# DRS_SCH-05-16.net
KiCad netlist of a schematic drawn in Altium Designer
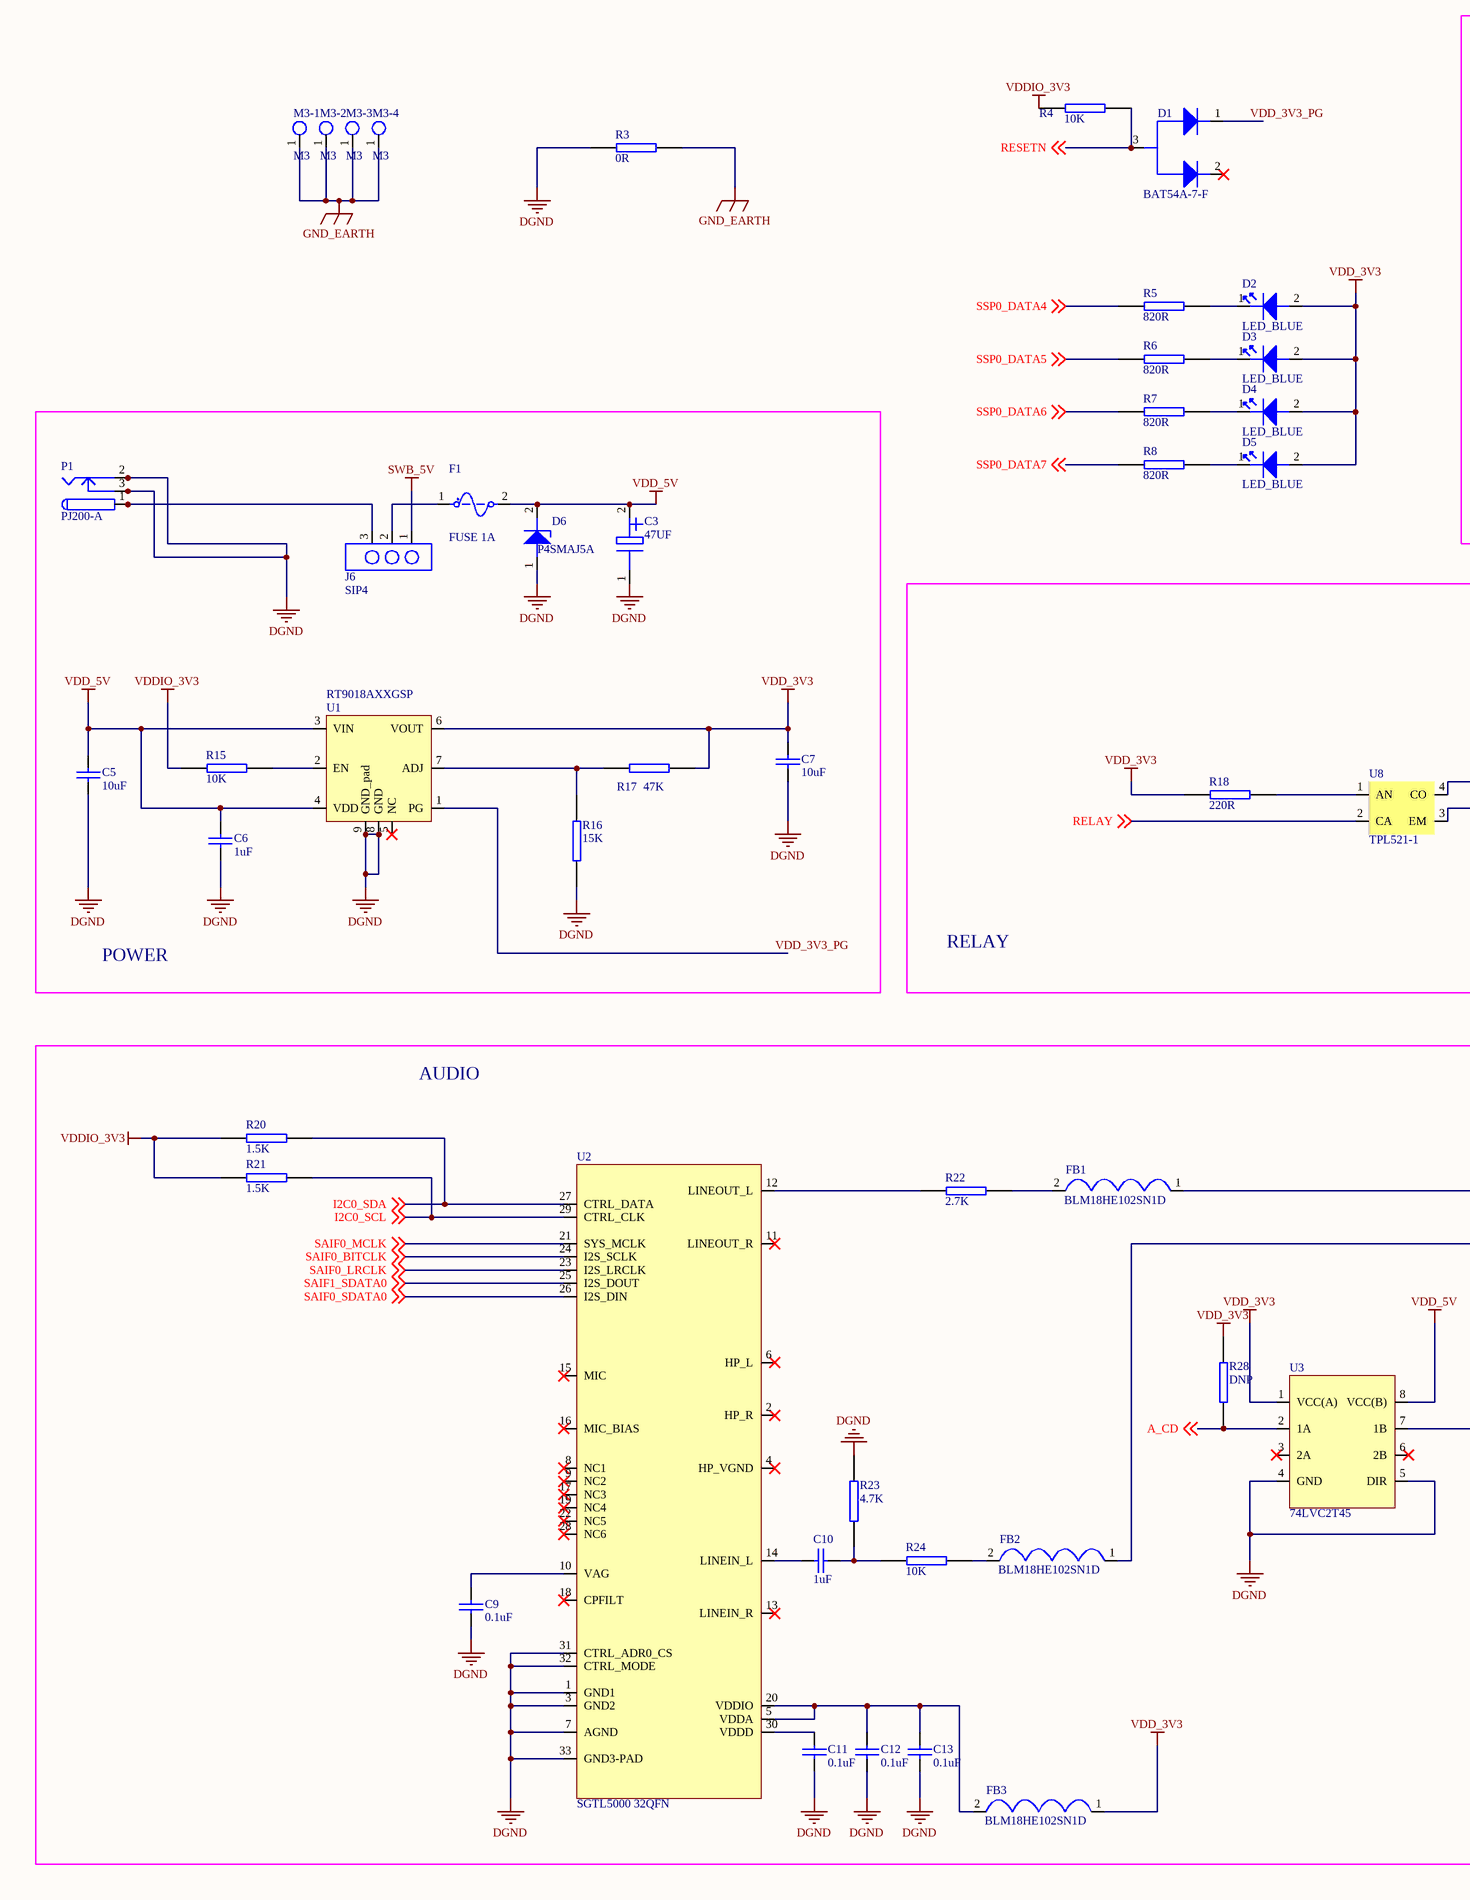
[diagram p0: DRS_SCH-05-16.SchDoc, left]
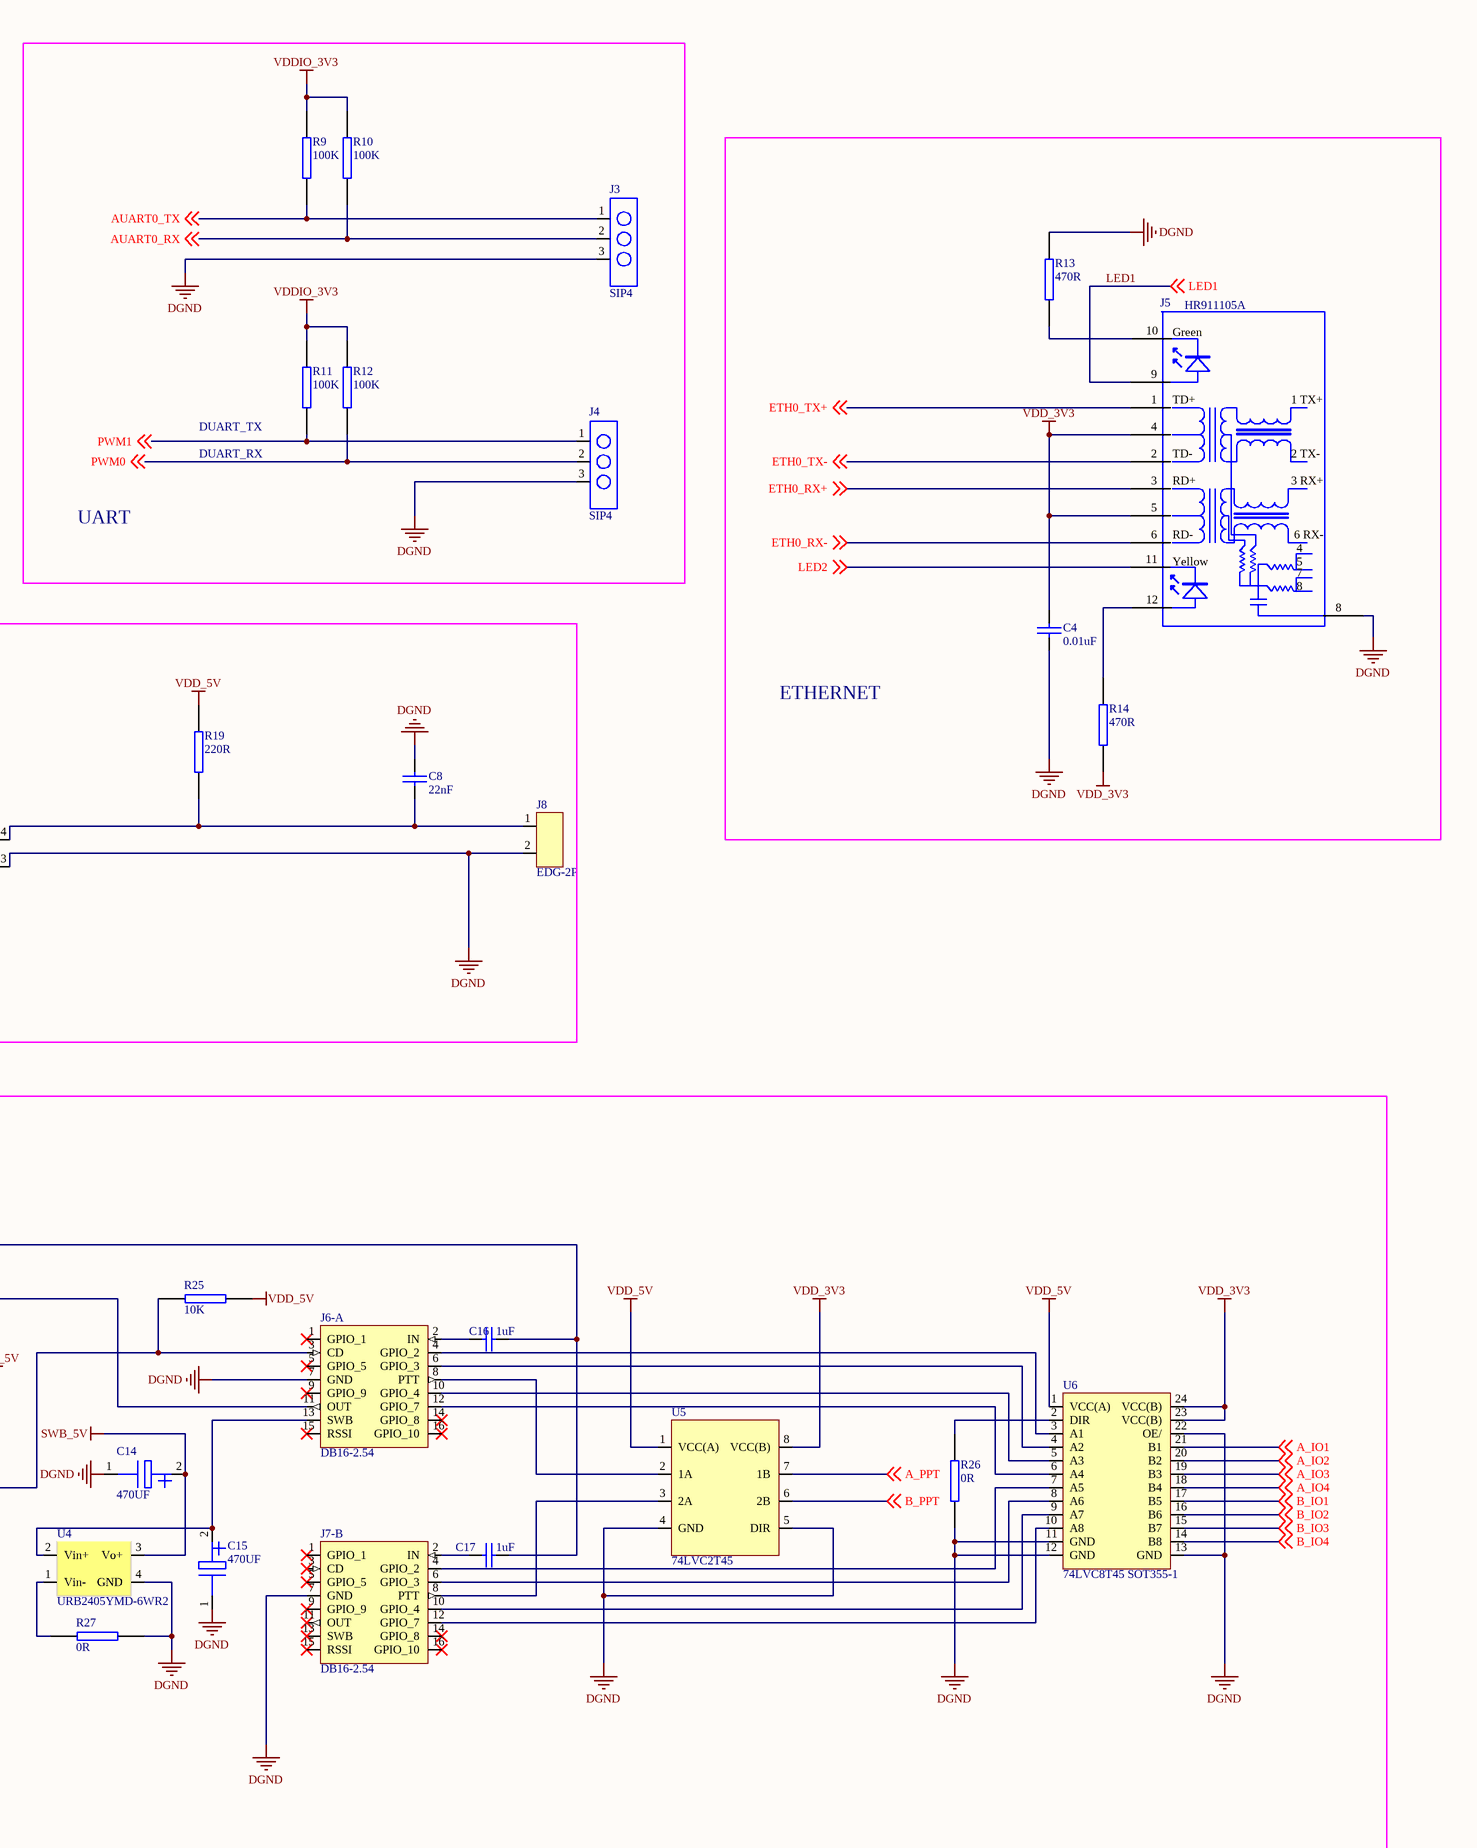
[diagram p1: DRS_SCH-05-16.SchDoc, right]

(export (version "E")
  (design (tool "Eeschema 10.0.6"))
  (components
    (comp (ref "C3") (value "47UF") (footprint "RVT6.3") (libsource (lib "Schlib1") (part "7343")))
    (comp (ref "C4")
      (value "0.01uF")
      (footprint "0603")
      (description "Capacitor")
      (libsource (lib "AirGateway") (part "CAP"))
    )
    (comp (ref "C5")
      (value "10uF")
      (footprint "C0805")
      (description "Capacitor")
      (libsource (lib "AirGateway") (part "CAP"))
    )
    (comp (ref "C6")
      (value "1uF")
      (footprint "0603")
      (description "Capacitor")
      (libsource (lib "AirGateway") (part "CAP"))
    )
    (comp (ref "C7")
      (value "10uF")
      (footprint "C0805")
      (description "Capacitor")
      (libsource (lib "AirGateway") (part "CAP"))
    )
    (comp (ref "C8")
      (value "22nF")
      (footprint "0603")
      (description "Capacitor")
      (libsource (lib "AirGateway") (part "CAP"))
    )
    (comp (ref "C9")
      (value "0.1uF")
      (footprint "0603")
      (description "Capacitor")
      (libsource (lib "AirGateway") (part "CAP"))
    )
    (comp (ref "C10")
      (value "1uF")
      (footprint "0603")
      (description "Capacitor")
      (libsource (lib "AirGateway") (part "CAP"))
    )
    (comp (ref "C11")
      (value "0.1uF")
      (footprint "0603")
      (description "Capacitor")
      (libsource (lib "AirGateway") (part "CAP"))
    )
    (comp (ref "C12")
      (value "0.1uF")
      (footprint "0603")
      (description "Capacitor")
      (libsource (lib "AirGateway") (part "CAP"))
    )
    (comp (ref "C13")
      (value "0.1uF")
      (footprint "0603")
      (description "Capacitor")
      (libsource (lib "AirGateway") (part "CAP"))
    )
    (comp (ref "C14") (value "470UF") (footprint "RVT8") (libsource (lib "Schlib1") (part "7343")))
    (comp (ref "C15") (value "470UF") (footprint "RVT8") (libsource (lib "Schlib1") (part "7343")))
    (comp (ref "C16")
      (value "1uF")
      (footprint "0603")
      (description "Capacitor")
      (libsource (lib "AirGateway") (part "CAP"))
    )
    (comp (ref "C17")
      (value "1uF")
      (footprint "0603")
      (description "Capacitor")
      (libsource (lib "AirGateway") (part "CAP"))
    )
    (comp (ref "D1") (value "BAT54A-7-F") (footprint "S9013") (libsource (lib "Schlib1") (part "BAT54A-7-F")))
    (comp (ref "D2") (value "LED_BLUE") (footprint "LED_BLUE") (libsource (lib "Schlib1") (part "LED_BLUE")))
    (comp (ref "D3") (value "LED_BLUE") (footprint "LED_BLUE") (libsource (lib "Schlib1") (part "LED_BLUE")))
    (comp (ref "D4") (value "LED_BLUE") (footprint "LED_BLUE") (libsource (lib "Schlib1") (part "LED_BLUE")))
    (comp (ref "D5") (value "LED_BLUE") (footprint "LED_BLUE") (libsource (lib "Schlib1") (part "LED_BLUE")))
    (comp (ref "D6") (value "P4SMAJ5A") (footprint "P4SMAJ5A") (libsource (lib "Schlib1") (part "P4SMAJ5A")))
    (comp (ref "F1") (value "FUSE 1A") (footprint "FUSE 1A") (libsource (lib "Schlib1") (part "FUSE 1A")))
    (comp (ref "FB1")
      (value "BLM18HE102SN1D")
      (footprint "0603")
      (libsource (lib "Schlib1") (part "BLM18HE102SN1D"))
    )
    (comp (ref "FB2")
      (value "BLM18HE102SN1D")
      (footprint "0603")
      (libsource (lib "Schlib1") (part "BLM18HE102SN1D"))
    )
    (comp (ref "FB3")
      (value "BLM18HE102SN1D")
      (footprint "0603")
      (libsource (lib "Schlib1") (part "BLM18HE102SN1D"))
    )
    (comp (ref "J3") (value "SIP4") (footprint "SIP3") (libsource (lib "Schlib1") (part "SIP4")))
    (comp (ref "J4") (value "SIP4") (footprint "SIP3") (libsource (lib "Schlib1") (part "SIP4")))
    (comp (ref "J5")
      (value "HR911105A")
      (footprint "HR911105A")
      (libsource (lib "AirGateway") (part "HR911105A"))
    )
    (comp (ref "J6") (value "SIP4") (footprint "SIP3") (libsource (lib "Schlib1") (part "SIP4")))
    (comp (ref "J6-A")
      (value "DB16-2.54")
      (footprint "DB2X8-2.54")
      (libsource (lib "Schlib1") (part "DB16-2.54"))
    )
    (comp (ref "J7-B")
      (value "DB16-2.54")
      (footprint "DB2X8-2.54")
      (libsource (lib "Schlib1") (part "DB16-2.54"))
    )
    (comp (ref "J8")
      (value "EDG-2P")
      (footprint "LZ1R-5.08-02P-140")
      (libsource (lib "Schlib1") (part "EDG-2P"))
    )
    (comp (ref "M3-1") (value "M3") (footprint "M3") (libsource (lib "Schlib1") (part "M3")))
    (comp (ref "M3-2") (value "M3") (footprint "M3") (libsource (lib "Schlib1") (part "M3")))
    (comp (ref "M3-3") (value "M3") (footprint "M3") (libsource (lib "Schlib1") (part "M3")))
    (comp (ref "M3-4") (value "M3") (footprint "M3") (libsource (lib "Schlib1") (part "M3")))
    (comp (ref "P1")
      (value "PJ200-A")
      (footprint "KLD-0202")
      (description "Low Voltage Power Supply Connector")
      (fields (field (name "PUBLISHER") "Altium Limited"))
      (libsource (lib "Miscellaneous Connectors") (part "PWR2.5"))
    )
    (comp (ref "R3") (value "0R") (footprint "0603") (libsource (lib "AirGateway") (part "RES2")))
    (comp (ref "R4") (value "10K") (footprint "0603") (libsource (lib "AirGateway") (part "RES2")))
    (comp (ref "R5") (value "820R") (footprint "0603") (libsource (lib "AirGateway") (part "RES2")))
    (comp (ref "R6") (value "820R") (footprint "0603") (libsource (lib "AirGateway") (part "RES2")))
    (comp (ref "R7") (value "820R") (footprint "0603") (libsource (lib "AirGateway") (part "RES2")))
    (comp (ref "R8") (value "820R") (footprint "0603") (libsource (lib "AirGateway") (part "RES2")))
    (comp (ref "R9") (value "100K") (footprint "0603") (libsource (lib "AirGateway") (part "RES2")))
    (comp (ref "R10") (value "100K") (footprint "0603") (libsource (lib "AirGateway") (part "RES2")))
    (comp (ref "R11") (value "100K") (footprint "0603") (libsource (lib "AirGateway") (part "RES2")))
    (comp (ref "R12") (value "100K") (footprint "0603") (libsource (lib "AirGateway") (part "RES2")))
    (comp (ref "R13") (value "470R") (footprint "0603") (libsource (lib "AirGateway") (part "RES2")))
    (comp (ref "R14") (value "470R") (footprint "0603") (libsource (lib "AirGateway") (part "RES2")))
    (comp (ref "R15") (value "10K") (footprint "0603") (libsource (lib "AirGateway") (part "RES2")))
    (comp (ref "R16") (value "15K") (footprint "0603") (libsource (lib "AirGateway") (part "RES2")))
    (comp (ref "R17") (value "47K") (footprint "0603") (libsource (lib "AirGateway") (part "RES2")))
    (comp (ref "R18") (value "220R") (footprint "0603") (libsource (lib "AirGateway") (part "RES2")))
    (comp (ref "R19") (value "220R") (footprint "0603") (libsource (lib "AirGateway") (part "RES2")))
    (comp (ref "R20") (value "1.5K") (footprint "0603") (libsource (lib "AirGateway") (part "RES2")))
    (comp (ref "R21") (value "1.5K") (footprint "0603") (libsource (lib "AirGateway") (part "RES2")))
    (comp (ref "R22") (value "2.7K") (footprint "0603") (libsource (lib "AirGateway") (part "RES2")))
    (comp (ref "R23") (value "4.7K") (footprint "0603") (libsource (lib "AirGateway") (part "RES2")))
    (comp (ref "R24") (value "10K") (footprint "0603") (libsource (lib "AirGateway") (part "RES2")))
    (comp (ref "R25") (value "10K") (footprint "0603") (libsource (lib "AirGateway") (part "RES2")))
    (comp (ref "R26") (value "0R") (footprint "0603") (libsource (lib "AirGateway") (part "RES2")))
    (comp (ref "R27") (value "0R") (footprint "0603") (libsource (lib "AirGateway") (part "RES2")))
    (comp (ref "R28") (value "DNP") (footprint "0603") (libsource (lib "AirGateway") (part "RES2")))
    (comp (ref "U1")
      (value "RT9018AXXGSP")
      (footprint "RT9018")
      (libsource (lib "Schlib1") (part "RT9018AXXGSP"))
    )
    (comp (ref "U2")
      (value "SGTL5000 32QFN")
      (footprint "SGTL5000 32QFN")
      (libsource (lib "Schlib1") (part "SGTL5000 32QFN"))
    )
    (comp (ref "U3")
      (value "74LVC2T45")
      (footprint "74LVC2T45")
      (libsource (lib "Schlib1") (part "74LVC2T45"))
    )
    (comp (ref "U4")
      (value "URB2405YMD-6WR2")
      (footprint "URB2405YMD-6WR2")
      (libsource (lib "Schlib1") (part "URB2405YMD-6WR2"))
    )
    (comp (ref "U5")
      (value "74LVC2T45")
      (footprint "74LVC2T45")
      (libsource (lib "Schlib1") (part "74LVC2T45"))
    )
    (comp (ref "U6")
      (value "74LVC8T45 SOT355-1")
      (footprint "74LVC8T245")
      (libsource (lib "Schlib1") (part "74LVC8T45 SOT355-1"))
    )
    (comp (ref "U8") (value "TPL521-1") (footprint "TPL521-1") (libsource (lib "Schlib1") (part "TPL521-1")))
  )
  (nets
    (net (code "1") (name "/VDD_3V3_PG") (class "Default")
      (node (ref "D1") (pin "1") (pintype "passive"))
      (node (ref "U1") (pin "1") (pinfunction "PG_1") (pintype "passive"))
    )
    (net (code "2") (name "AUART0_RX") (class "Default")
      (node (ref "J3") (pin "2") (pintype "passive"))
      (node (ref "R10") (pin "1") (pinfunction "1_1") (pintype "passive"))
    )
    (net (code "3") (name "AUART0_TX") (class "Default")
      (node (ref "J3") (pin "1") (pintype "passive"))
      (node (ref "R9") (pin "1") (pinfunction "1_1") (pintype "passive"))
    )
    (net (code "4") (name "A_CD") (class "Default")
      (node (ref "R28") (pin "2") (pinfunction "2_2") (pintype "passive"))
      (node (ref "U3") (pin "2") (pinfunction "1A_2") (pintype "passive"))
    )
    (net (code "5") (name "A_IO1") (class "Default")
      (node (ref "U6") (pin "21") (pinfunction "B1_21") (pintype "passive"))
    )
    (net (code "6") (name "A_IO2") (class "Default")
      (node (ref "U6") (pin "20") (pinfunction "B2_20") (pintype "passive"))
    )
    (net (code "7") (name "A_IO3") (class "Default")
      (node (ref "U6") (pin "19") (pinfunction "B3_19") (pintype "passive"))
    )
    (net (code "8") (name "A_IO4") (class "Default")
      (node (ref "U6") (pin "18") (pinfunction "B4_18") (pintype "passive"))
    )
    (net (code "9") (name "A_PPT") (class "Default")
      (node (ref "U5") (pin "7") (pinfunction "1B_7") (pintype "passive"))
    )
    (net (code "10") (name "B_IO1") (class "Default")
      (node (ref "U6") (pin "17") (pinfunction "B5_17") (pintype "passive"))
    )
    (net (code "11") (name "B_IO2") (class "Default")
      (node (ref "U6") (pin "16") (pinfunction "B6_16") (pintype "passive"))
    )
    (net (code "12") (name "B_IO3") (class "Default")
      (node (ref "U6") (pin "15") (pinfunction "B7_15") (pintype "passive"))
    )
    (net (code "13") (name "B_IO4") (class "Default")
      (node (ref "U6") (pin "14") (pinfunction "B8_14") (pintype "passive"))
    )
    (net (code "14") (name "B_PPT") (class "Default")
      (node (ref "U5") (pin "6") (pinfunction "2B_6") (pintype "passive"))
    )
    (net (code "15") (name "DGND") (class "Default")
      (node (ref "C11") (pin "2") (pinfunction "2_2") (pintype "passive"))
      (node (ref "C12") (pin "2") (pinfunction "2_2") (pintype "passive"))
      (node (ref "C13") (pin "2") (pinfunction "2_2") (pintype "passive"))
      (node (ref "C14") (pin "1") (pintype "passive"))
      (node (ref "C15") (pin "1") (pintype "passive"))
      (node (ref "C3") (pin "1") (pintype "passive"))
      (node (ref "C4") (pin "2") (pinfunction "2_2") (pintype "passive"))
      (node (ref "C5") (pin "2") (pinfunction "2_2") (pintype "passive"))
      (node (ref "C6") (pin "2") (pinfunction "2_2") (pintype "passive"))
      (node (ref "C7") (pin "2") (pinfunction "2_2") (pintype "passive"))
      (node (ref "C8") (pin "1") (pinfunction "1_1") (pintype "passive"))
      (node (ref "C9") (pin "1") (pinfunction "1_1") (pintype "passive"))
      (node (ref "D6") (pin "1") (pintype "passive"))
      (node (ref "J3") (pin "3") (pintype "passive"))
      (node (ref "J4") (pin "3") (pintype "passive"))
      (node (ref "J5") (pin "8") (pintype "passive"))
      (node (ref "J6-A") (pin "7") (pinfunction "GND_7") (pintype "passive"))
      (node (ref "J7-B") (pin "7") (pinfunction "GND_7") (pintype "passive"))
      (node (ref "J8") (pin "2") (pintype "passive"))
      (node (ref "P1") (pin "2") (pinfunction "2_2") (pintype "power_in"))
      (node (ref "P1") (pin "2A") (pinfunction "2A_2A") (pintype "power_in"))
      (node (ref "P1") (pin "2B") (pinfunction "2B_2B") (pintype "power_in"))
      (node (ref "P1") (pin "3") (pinfunction "3_3") (pintype "power_in"))
      (node (ref "P1") (pin "3A") (pinfunction "3A_3A") (pintype "power_in"))
      (node (ref "P1") (pin "3B") (pinfunction "3B_3B") (pintype "power_in"))
      (node (ref "R13") (pin "2") (pinfunction "2_2") (pintype "passive"))
      (node (ref "R16") (pin "1") (pinfunction "1_1") (pintype "passive"))
      (node (ref "R23") (pin "2") (pinfunction "2_2") (pintype "passive"))
      (node (ref "R26") (pin "1") (pinfunction "1_1") (pintype "passive"))
      (node (ref "R27") (pin "1") (pinfunction "1_1") (pintype "passive"))
      (node (ref "R3") (pin "2") (pinfunction "2_2") (pintype "passive"))
      (node (ref "U1") (pin "8") (pinfunction "GND_8") (pintype "passive"))
      (node (ref "U1") (pin "9") (pinfunction "GND_pad_9") (pintype "passive"))
      (node (ref "U2") (pin "1") (pinfunction "GND1_1") (pintype "passive"))
      (node (ref "U2") (pin "3") (pinfunction "GND2_3") (pintype "passive"))
      (node (ref "U2") (pin "31") (pinfunction "CTRL_ADR0_CS_31") (pintype "passive"))
      (node (ref "U2") (pin "32") (pinfunction "CTRL_MODE_32") (pintype "passive"))
      (node (ref "U2") (pin "33") (pinfunction "GND3-PAD_33") (pintype "passive"))
      (node (ref "U2") (pin "7") (pinfunction "AGND_7") (pintype "passive"))
      (node (ref "U3") (pin "4") (pinfunction "GND_4") (pintype "passive"))
      (node (ref "U3") (pin "5") (pinfunction "DIR_5") (pintype "passive"))
      (node (ref "U4") (pin "4") (pinfunction "GND_4") (pintype "passive"))
      (node (ref "U5") (pin "4") (pinfunction "GND_4") (pintype "passive"))
      (node (ref "U5") (pin "5") (pinfunction "DIR_5") (pintype "passive"))
      (node (ref "U6") (pin "11") (pinfunction "GND_11") (pintype "passive"))
      (node (ref "U6") (pin "12") (pinfunction "GND_12") (pintype "passive"))
      (node (ref "U6") (pin "13") (pinfunction "GND_13") (pintype "passive"))
      (node (ref "U6") (pin "22") (pinfunction "OE/_22") (pintype "passive"))
      (node (ref "U8") (pin "3") (pinfunction "EM_3") (pintype "passive"))
    )
    (net (code "16") (name "ETH0_RX+") (class "Default") (node (ref "J5") (pin "3") (pintype "passive")))
    (net (code "17") (name "ETH0_RX-") (class "Default") (node (ref "J5") (pin "6") (pintype "passive")))
    (net (code "18") (name "ETH0_TX+") (class "Default") (node (ref "J5") (pin "1") (pintype "passive")))
    (net (code "19") (name "ETH0_TX-") (class "Default") (node (ref "J5") (pin "2") (pintype "passive")))
    (net (code "20") (name "GND_EARTH") (class "Default")
      (node (ref "M3-1") (pin "1") (pintype "passive"))
      (node (ref "M3-2") (pin "1") (pintype "passive"))
      (node (ref "M3-3") (pin "1") (pintype "passive"))
      (node (ref "M3-4") (pin "1") (pintype "passive"))
      (node (ref "R3") (pin "1") (pinfunction "1_1") (pintype "passive"))
    )
    (net (code "21") (name "I2C0_SCL") (class "Default")
      (node (ref "R21") (pin "1") (pinfunction "1_1") (pintype "passive"))
      (node (ref "U2") (pin "29") (pinfunction "CTRL_CLK_29") (pintype "passive"))
    )
    (net (code "22") (name "I2C0_SDA") (class "Default")
      (node (ref "R20") (pin "1") (pinfunction "1_1") (pintype "passive"))
      (node (ref "U2") (pin "27") (pinfunction "CTRL_DATA_27") (pintype "passive"))
    )
    (net (code "23") (name "LED1") (class "Default") (node (ref "J5") (pin "9") (pintype "passive")))
    (net (code "24") (name "LED2") (class "Default") (node (ref "J5") (pin "11") (pintype "passive")))
    (net (code "25") (name "Net-(C10-Pad1)") (class "Default")
      (node (ref "C10") (pin "1") (pinfunction "1_1") (pintype "passive"))
      (node (ref "R23") (pin "1") (pinfunction "1_1") (pintype "passive"))
      (node (ref "R24") (pin "2") (pinfunction "2_2") (pintype "passive"))
    )
    (net (code "26") (name "Net-(C16-Pad1)") (class "Default")
      (node (ref "C16") (pin "1") (pinfunction "1_1") (pintype "passive"))
      (node (ref "C17") (pin "1") (pinfunction "1_1") (pintype "passive"))
      (node (ref "FB1") (pin "1") (pintype "passive"))
    )
    (net (code "27") (name "Net-(D2-Pad1)") (class "Default")
      (node (ref "D2") (pin "1") (pintype "passive"))
      (node (ref "R5") (pin "2") (pinfunction "2_2") (pintype "passive"))
    )
    (net (code "28") (name "Net-(D3-Pad1)") (class "Default")
      (node (ref "D3") (pin "1") (pintype "passive"))
      (node (ref "R6") (pin "2") (pinfunction "2_2") (pintype "passive"))
    )
    (net (code "29") (name "Net-(D4-Pad1)") (class "Default")
      (node (ref "D4") (pin "1") (pintype "passive"))
      (node (ref "R7") (pin "2") (pinfunction "2_2") (pintype "passive"))
    )
    (net (code "30") (name "Net-(D5-Pad1)") (class "Default")
      (node (ref "D5") (pin "1") (pintype "passive"))
      (node (ref "R8") (pin "2") (pinfunction "2_2") (pintype "passive"))
    )
    (net (code "31") (name "Net-(F1-Pad1)") (class "Default")
      (node (ref "F1") (pin "1") (pintype "passive"))
      (node (ref "J6") (pin "2") (pintype "passive"))
    )
    (net (code "32") (name "Net-(FB1-Pad2)") (class "Default")
      (node (ref "FB1") (pin "2") (pintype "passive"))
      (node (ref "R22") (pin "1") (pinfunction "1_1") (pintype "passive"))
    )
    (net (code "33") (name "Net-(FB2-Pad2)") (class "Default")
      (node (ref "FB2") (pin "2") (pintype "passive"))
      (node (ref "R24") (pin "1") (pinfunction "1_1") (pintype "passive"))
    )
    (net (code "34") (name "Net-(J5-Pad10)") (class "Default")
      (node (ref "J5") (pin "10") (pintype "passive"))
      (node (ref "R13") (pin "1") (pinfunction "1_1") (pintype "passive"))
    )
    (net (code "35") (name "Net-(J5-Pad12)") (class "Default")
      (node (ref "J5") (pin "12") (pintype "passive"))
      (node (ref "R14") (pin "2") (pinfunction "2_2") (pintype "passive"))
    )
    (net (code "36") (name "Net-(J6-A-CD)") (class "Default")
      (node (ref "J6-A") (pin "3") (pinfunction "CD_3") (pintype "input"))
      (node (ref "R25") (pin "2") (pinfunction "2_2") (pintype "passive"))
      (node (ref "U3") (pin "7") (pinfunction "1B_7") (pintype "passive"))
    )
    (net (code "37") (name "Net-(J6-A-GPIO_2)") (class "Default")
      (node (ref "J6-A") (pin "4") (pinfunction "GPIO_2_4") (pintype "passive"))
      (node (ref "U6") (pin "3") (pinfunction "A1_3") (pintype "passive"))
    )
    (net (code "38") (name "Net-(J6-A-GPIO_3)") (class "Default")
      (node (ref "J6-A") (pin "6") (pinfunction "GPIO_3_6") (pintype "passive"))
      (node (ref "U6") (pin "4") (pinfunction "A2_4") (pintype "passive"))
    )
    (net (code "39") (name "Net-(J6-A-GPIO_4)") (class "Default")
      (node (ref "J6-A") (pin "10") (pinfunction "GPIO_4_10") (pintype "passive"))
      (node (ref "U6") (pin "5") (pinfunction "A3_5") (pintype "passive"))
    )
    (net (code "40") (name "Net-(J6-A-GPIO_7)") (class "Default")
      (node (ref "J6-A") (pin "12") (pinfunction "GPIO_7_12") (pintype "passive"))
      (node (ref "U6") (pin "6") (pinfunction "A4_6") (pintype "passive"))
    )
    (net (code "41") (name "Net-(J6-A-IN)") (class "Default")
      (node (ref "C16") (pin "2") (pinfunction "2_2") (pintype "passive"))
      (node (ref "J6-A") (pin "2") (pinfunction "IN_2") (pintype "input"))
    )
    (net (code "42") (name "Net-(J6-A-OUT)") (class "Default")
      (node (ref "FB2") (pin "1") (pintype "passive"))
      (node (ref "J6-A") (pin "11") (pinfunction "OUT_11") (pintype "output"))
    )
    (net (code "43") (name "Net-(J6-A-PTT)") (class "Default")
      (node (ref "J6-A") (pin "8") (pinfunction "PTT_8") (pintype "output"))
      (node (ref "U5") (pin "2") (pinfunction "1A_2") (pintype "passive"))
    )
    (net (code "44") (name "Net-(J6-A-SWB)") (class "Default")
      (node (ref "C15") (pin "2") (pintype "passive"))
      (node (ref "J6-A") (pin "13") (pinfunction "SWB_13") (pintype "power_in"))
      (node (ref "U4") (pin "2") (pinfunction "Vin+_2") (pintype "passive"))
    )
    (net (code "45") (name "Net-(J6-Pad3)") (class "Default")
      (node (ref "J6") (pin "3") (pintype "passive"))
      (node (ref "P1") (pin "1") (pinfunction "1_1") (pintype "power_in"))
      (node (ref "P1") (pin "1A") (pinfunction "1A_1A") (pintype "power_in"))
      (node (ref "P1") (pin "1B") (pinfunction "1B_1B") (pintype "power_in"))
    )
    (net (code "46") (name "Net-(J7-B-GPIO_2)") (class "Default")
      (node (ref "J7-B") (pin "4") (pinfunction "GPIO_2_4") (pintype "passive"))
      (node (ref "U6") (pin "7") (pinfunction "A5_7") (pintype "passive"))
    )
    (net (code "47") (name "Net-(J7-B-GPIO_3)") (class "Default")
      (node (ref "J7-B") (pin "6") (pinfunction "GPIO_3_6") (pintype "passive"))
      (node (ref "U6") (pin "8") (pinfunction "A6_8") (pintype "passive"))
    )
    (net (code "48") (name "Net-(J7-B-GPIO_4)") (class "Default")
      (node (ref "J7-B") (pin "10") (pinfunction "GPIO_4_10") (pintype "passive"))
      (node (ref "U6") (pin "9") (pinfunction "A7_9") (pintype "passive"))
    )
    (net (code "49") (name "Net-(J7-B-GPIO_7)") (class "Default")
      (node (ref "J7-B") (pin "12") (pinfunction "GPIO_7_12") (pintype "passive"))
      (node (ref "U6") (pin "10") (pinfunction "A8_10") (pintype "passive"))
    )
    (net (code "50") (name "Net-(J7-B-IN)") (class "Default")
      (node (ref "C17") (pin "2") (pinfunction "2_2") (pintype "passive"))
      (node (ref "J7-B") (pin "2") (pinfunction "IN_2") (pintype "input"))
    )
    (net (code "51") (name "Net-(J7-B-PTT)") (class "Default")
      (node (ref "J7-B") (pin "8") (pinfunction "PTT_8") (pintype "output"))
      (node (ref "U5") (pin "3") (pinfunction "2A_3") (pintype "passive"))
    )
    (net (code "52") (name "Net-(U1-ADJ)") (class "Default")
      (node (ref "R16") (pin "2") (pinfunction "2_2") (pintype "passive"))
      (node (ref "R17") (pin "1") (pinfunction "1_1") (pintype "passive"))
      (node (ref "U1") (pin "7") (pinfunction "ADJ_7") (pintype "passive"))
    )
    (net (code "53") (name "Net-(U1-EN)") (class "Default")
      (node (ref "R15") (pin "1") (pinfunction "1_1") (pintype "passive"))
      (node (ref "U1") (pin "2") (pinfunction "EN_2") (pintype "passive"))
    )
    (net (code "54") (name "Net-(U2-LINEIN_L)") (class "Default")
      (node (ref "C10") (pin "2") (pinfunction "2_2") (pintype "passive"))
      (node (ref "U2") (pin "14") (pinfunction "LINEIN_L_14") (pintype "passive"))
    )
    (net (code "55") (name "Net-(U2-LINEOUT_L)") (class "Default")
      (node (ref "R22") (pin "2") (pinfunction "2_2") (pintype "passive"))
      (node (ref "U2") (pin "12") (pinfunction "LINEOUT_L_12") (pintype "passive"))
    )
    (net (code "56") (name "Net-(U2-VAG)") (class "Default")
      (node (ref "C9") (pin "2") (pinfunction "2_2") (pintype "passive"))
      (node (ref "U2") (pin "10") (pinfunction "VAG_10") (pintype "passive"))
    )
    (net (code "57") (name "Net-(U2-VDDA)") (class "Default")
      (node (ref "C12") (pin "1") (pinfunction "1_1") (pintype "passive"))
      (node (ref "C13") (pin "1") (pinfunction "1_1") (pintype "passive"))
      (node (ref "FB3") (pin "2") (pintype "passive"))
      (node (ref "U2") (pin "20") (pinfunction "VDDIO_20") (pintype "passive"))
      (node (ref "U2") (pin "5") (pinfunction "VDDA_5") (pintype "passive"))
    )
    (net (code "58") (name "Net-(U2-VDDD)") (class "Default")
      (node (ref "C11") (pin "1") (pinfunction "1_1") (pintype "passive"))
      (node (ref "U2") (pin "30") (pinfunction "VDDD_30") (pintype "passive"))
    )
    (net (code "59") (name "Net-(U4-Vin-)") (class "Default")
      (node (ref "R27") (pin "2") (pinfunction "2_2") (pintype "passive"))
      (node (ref "U4") (pin "1") (pinfunction "Vin-_1") (pintype "passive"))
    )
    (net (code "60") (name "Net-(U6-DIR)") (class "Default")
      (node (ref "R26") (pin "2") (pinfunction "2_2") (pintype "passive"))
      (node (ref "U6") (pin "2") (pinfunction "DIR_2") (pintype "passive"))
    )
    (net (code "61") (name "Net-(U8-AN)") (class "Default")
      (node (ref "R18") (pin "2") (pinfunction "2_2") (pintype "passive"))
      (node (ref "U8") (pin "1") (pinfunction "AN_1") (pintype "passive"))
    )
    (net (code "62") (name "Net-(U8-CO)") (class "Default")
      (node (ref "C8") (pin "2") (pinfunction "2_2") (pintype "passive"))
      (node (ref "J8") (pin "1") (pintype "passive"))
      (node (ref "R19") (pin "1") (pinfunction "1_1") (pintype "passive"))
      (node (ref "U8") (pin "4") (pinfunction "CO_4") (pintype "passive"))
    )
    (net (code "63") (name "PWM0") (class "Default")
      (node (ref "J4") (pin "2") (pintype "passive"))
      (node (ref "R12") (pin "1") (pinfunction "1_1") (pintype "passive"))
    )
    (net (code "64") (name "PWM1") (class "Default")
      (node (ref "J4") (pin "1") (pintype "passive"))
      (node (ref "R11") (pin "1") (pinfunction "1_1") (pintype "passive"))
    )
    (net (code "65") (name "RELAY") (class "Default")
      (node (ref "U8") (pin "2") (pinfunction "CA_2") (pintype "passive"))
    )
    (net (code "66") (name "RESETN") (class "Default")
      (node (ref "D1") (pin "3") (pintype "passive"))
      (node (ref "R4") (pin "2") (pinfunction "2_2") (pintype "passive"))
    )
    (net (code "67") (name "SAIF0_BITCLK") (class "Default")
      (node (ref "U2") (pin "24") (pinfunction "I2S_SCLK_24") (pintype "passive"))
    )
    (net (code "68") (name "SAIF0_LRCLK") (class "Default")
      (node (ref "U2") (pin "23") (pinfunction "I2S_LRCLK_23") (pintype "passive"))
    )
    (net (code "69") (name "SAIF0_MCLK") (class "Default")
      (node (ref "U2") (pin "21") (pinfunction "SYS_MCLK_21") (pintype "passive"))
    )
    (net (code "70") (name "SAIF0_SDATA0") (class "Default")
      (node (ref "U2") (pin "26") (pinfunction "I2S_DIN_26") (pintype "passive"))
    )
    (net (code "71") (name "SAIF1_SDATA0") (class "Default")
      (node (ref "U2") (pin "25") (pinfunction "I2S_DOUT_25") (pintype "passive"))
    )
    (net (code "72") (name "SSP0_DATA4") (class "Default")
      (node (ref "R5") (pin "1") (pinfunction "1_1") (pintype "passive"))
    )
    (net (code "73") (name "SSP0_DATA5") (class "Default")
      (node (ref "R6") (pin "1") (pinfunction "1_1") (pintype "passive"))
    )
    (net (code "74") (name "SSP0_DATA6") (class "Default")
      (node (ref "R7") (pin "1") (pinfunction "1_1") (pintype "passive"))
    )
    (net (code "75") (name "SSP0_DATA7") (class "Default")
      (node (ref "R8") (pin "1") (pinfunction "1_1") (pintype "passive"))
    )
    (net (code "76") (name "SWB_5V") (class "Default")
      (node (ref "C14") (pin "2") (pintype "passive"))
      (node (ref "J6") (pin "1") (pintype "passive"))
      (node (ref "U4") (pin "3") (pinfunction "Vo+_3") (pintype "passive"))
    )
    (net (code "77") (name "VDDIO_3V3") (class "Default")
      (node (ref "R10") (pin "2") (pinfunction "2_2") (pintype "passive"))
      (node (ref "R11") (pin "2") (pinfunction "2_2") (pintype "passive"))
      (node (ref "R12") (pin "2") (pinfunction "2_2") (pintype "passive"))
      (node (ref "R15") (pin "2") (pinfunction "2_2") (pintype "passive"))
      (node (ref "R20") (pin "2") (pinfunction "2_2") (pintype "passive"))
      (node (ref "R21") (pin "2") (pinfunction "2_2") (pintype "passive"))
      (node (ref "R4") (pin "1") (pinfunction "1_1") (pintype "passive"))
      (node (ref "R9") (pin "2") (pinfunction "2_2") (pintype "passive"))
    )
    (net (code "78") (name "VDD_3V3") (class "Default")
      (node (ref "C4") (pin "1") (pinfunction "1_1") (pintype "passive"))
      (node (ref "C7") (pin "1") (pinfunction "1_1") (pintype "passive"))
      (node (ref "D2") (pin "2") (pintype "passive"))
      (node (ref "D3") (pin "2") (pintype "passive"))
      (node (ref "D4") (pin "2") (pintype "passive"))
      (node (ref "D5") (pin "2") (pintype "passive"))
      (node (ref "FB3") (pin "1") (pintype "passive"))
      (node (ref "J5") (pin "4") (pintype "passive"))
      (node (ref "J5") (pin "5") (pintype "passive"))
      (node (ref "R14") (pin "1") (pinfunction "1_1") (pintype "passive"))
      (node (ref "R17") (pin "2") (pinfunction "2_2") (pintype "passive"))
      (node (ref "R18") (pin "1") (pinfunction "1_1") (pintype "passive"))
      (node (ref "R28") (pin "1") (pinfunction "1_1") (pintype "passive"))
      (node (ref "U1") (pin "6") (pinfunction "VOUT_6") (pintype "passive"))
      (node (ref "U3") (pin "1") (pinfunction "VCC(A)_1") (pintype "passive"))
      (node (ref "U5") (pin "8") (pinfunction "VCC(B)_8") (pintype "passive"))
      (node (ref "U6") (pin "23") (pinfunction "VCC(B)_23") (pintype "passive"))
      (node (ref "U6") (pin "24") (pinfunction "VCC(B)_24") (pintype "passive"))
    )
    (net (code "79") (name "VDD_5V") (class "Default")
      (node (ref "C3") (pin "2") (pintype "passive"))
      (node (ref "C5") (pin "1") (pinfunction "1_1") (pintype "passive"))
      (node (ref "C6") (pin "1") (pinfunction "1_1") (pintype "passive"))
      (node (ref "D6") (pin "2") (pintype "passive"))
      (node (ref "F1") (pin "2") (pintype "passive"))
      (node (ref "R19") (pin "2") (pinfunction "2_2") (pintype "passive"))
      (node (ref "R25") (pin "1") (pinfunction "1_1") (pintype "passive"))
      (node (ref "U1") (pin "3") (pinfunction "VIN_3") (pintype "passive"))
      (node (ref "U1") (pin "4") (pinfunction "VDD_4") (pintype "passive"))
      (node (ref "U3") (pin "8") (pinfunction "VCC(B)_8") (pintype "passive"))
      (node (ref "U5") (pin "1") (pinfunction "VCC(A)_1") (pintype "passive"))
      (node (ref "U6") (pin "1") (pinfunction "VCC(A)_1") (pintype "passive"))
    )
    (net (code "80") (name "unconnected-(D1-Pad2)") (class "Default")
      (node (ref "D1") (pin "2") (pintype "passive+no_connect"))
    )
    (net (code "81") (name "unconnected-(J6-A-GPIO_1-Pad1)") (class "Default")
      (node (ref "J6-A") (pin "1") (pinfunction "GPIO_1_1") (pintype "passive+no_connect"))
    )
    (net (code "82") (name "unconnected-(J6-A-GPIO_5-Pad5)") (class "Default")
      (node (ref "J6-A") (pin "5") (pinfunction "GPIO_5_5") (pintype "passive+no_connect"))
    )
    (net (code "83") (name "unconnected-(J6-A-GPIO_8-Pad14)") (class "Default")
      (node (ref "J6-A") (pin "14") (pinfunction "GPIO_8_14") (pintype "passive+no_connect"))
    )
    (net (code "84") (name "unconnected-(J6-A-GPIO_9-Pad9)") (class "Default")
      (node (ref "J6-A") (pin "9") (pinfunction "GPIO_9_9") (pintype "passive+no_connect"))
    )
    (net (code "85") (name "unconnected-(J6-A-GPIO_10-Pad16)") (class "Default")
      (node (ref "J6-A") (pin "16") (pinfunction "GPIO_10_16") (pintype "passive+no_connect"))
    )
    (net (code "86") (name "unconnected-(J6-A-RSSI-Pad15)") (class "Default")
      (node (ref "J6-A") (pin "15") (pinfunction "RSSI_15") (pintype "passive+no_connect"))
    )
    (net (code "87") (name "unconnected-(J7-B-CD-Pad3)") (class "Default")
      (node (ref "J7-B") (pin "3") (pinfunction "CD_3") (pintype "input+no_connect"))
    )
    (net (code "88") (name "unconnected-(J7-B-GPIO_1-Pad1)") (class "Default")
      (node (ref "J7-B") (pin "1") (pinfunction "GPIO_1_1") (pintype "passive+no_connect"))
    )
    (net (code "89") (name "unconnected-(J7-B-GPIO_5-Pad5)") (class "Default")
      (node (ref "J7-B") (pin "5") (pinfunction "GPIO_5_5") (pintype "passive+no_connect"))
    )
    (net (code "90") (name "unconnected-(J7-B-GPIO_8-Pad14)") (class "Default")
      (node (ref "J7-B") (pin "14") (pinfunction "GPIO_8_14") (pintype "passive+no_connect"))
    )
    (net (code "91") (name "unconnected-(J7-B-GPIO_9-Pad9)") (class "Default")
      (node (ref "J7-B") (pin "9") (pinfunction "GPIO_9_9") (pintype "passive+no_connect"))
    )
    (net (code "92") (name "unconnected-(J7-B-GPIO_10-Pad16)") (class "Default")
      (node (ref "J7-B") (pin "16") (pinfunction "GPIO_10_16") (pintype "passive+no_connect"))
    )
    (net (code "93") (name "unconnected-(J7-B-OUT-Pad11)") (class "Default")
      (node (ref "J7-B") (pin "11") (pinfunction "OUT_11") (pintype "output+no_connect"))
    )
    (net (code "94") (name "unconnected-(J7-B-RSSI-Pad15)") (class "Default")
      (node (ref "J7-B") (pin "15") (pinfunction "RSSI_15") (pintype "passive+no_connect"))
    )
    (net (code "95") (name "unconnected-(J7-B-SWB-Pad13)") (class "Default")
      (node (ref "J7-B") (pin "13") (pinfunction "SWB_13") (pintype "power_in+no_connect"))
    )
    (net (code "96") (name "unconnected-(U1-NC-Pad5)") (class "Default")
      (node (ref "U1") (pin "5") (pinfunction "NC_5") (pintype "passive+no_connect"))
    )
    (net (code "97") (name "unconnected-(U2-CPFILT-Pad18)") (class "Default")
      (node (ref "U2") (pin "18") (pinfunction "CPFILT_18") (pintype "passive+no_connect"))
    )
    (net (code "98") (name "unconnected-(U2-HP_L-Pad6)") (class "Default")
      (node (ref "U2") (pin "6") (pinfunction "HP_L_6") (pintype "passive+no_connect"))
    )
    (net (code "99") (name "unconnected-(U2-HP_R-Pad2)") (class "Default")
      (node (ref "U2") (pin "2") (pinfunction "HP_R_2") (pintype "passive+no_connect"))
    )
    (net (code "100") (name "unconnected-(U2-HP_VGND-Pad4)") (class "Default")
      (node (ref "U2") (pin "4") (pinfunction "HP_VGND_4") (pintype "passive+no_connect"))
    )
    (net (code "101") (name "unconnected-(U2-LINEIN_R-Pad13)") (class "Default")
      (node (ref "U2") (pin "13") (pinfunction "LINEIN_R_13") (pintype "passive+no_connect"))
    )
    (net (code "102") (name "unconnected-(U2-LINEOUT_R-Pad11)") (class "Default")
      (node (ref "U2") (pin "11") (pinfunction "LINEOUT_R_11") (pintype "passive+no_connect"))
    )
    (net (code "103") (name "unconnected-(U2-MIC-Pad15)") (class "Default")
      (node (ref "U2") (pin "15") (pinfunction "MIC_15") (pintype "passive+no_connect"))
    )
    (net (code "104") (name "unconnected-(U2-MIC_BIAS-Pad16)") (class "Default")
      (node (ref "U2") (pin "16") (pinfunction "MIC_BIAS_16") (pintype "passive+no_connect"))
    )
    (net (code "105") (name "unconnected-(U2-NC1-Pad8)") (class "Default")
      (node (ref "U2") (pin "8") (pinfunction "NC1_8") (pintype "passive+no_connect"))
    )
    (net (code "106") (name "unconnected-(U2-NC2-Pad9)") (class "Default")
      (node (ref "U2") (pin "9") (pinfunction "NC2_9") (pintype "passive+no_connect"))
    )
    (net (code "107") (name "unconnected-(U2-NC3-Pad17)") (class "Default")
      (node (ref "U2") (pin "17") (pinfunction "NC3_17") (pintype "passive+no_connect"))
    )
    (net (code "108") (name "unconnected-(U2-NC4-Pad19)") (class "Default")
      (node (ref "U2") (pin "19") (pinfunction "NC4_19") (pintype "passive+no_connect"))
    )
    (net (code "109") (name "unconnected-(U2-NC5-Pad22)") (class "Default")
      (node (ref "U2") (pin "22") (pinfunction "NC5_22") (pintype "passive+no_connect"))
    )
    (net (code "110") (name "unconnected-(U2-NC6-Pad28)") (class "Default")
      (node (ref "U2") (pin "28") (pinfunction "NC6_28") (pintype "passive+no_connect"))
    )
    (net (code "111") (name "unconnected-(U3-2A-Pad3)") (class "Default")
      (node (ref "U3") (pin "3") (pinfunction "2A_3") (pintype "passive+no_connect"))
    )
    (net (code "112") (name "unconnected-(U3-2B-Pad6)") (class "Default")
      (node (ref "U3") (pin "6") (pinfunction "2B_6") (pintype "passive+no_connect"))
    )
  )
)
